# Shruthi-Analog-dev.net
KiCad netlist of a schematic drawn in EAGLE
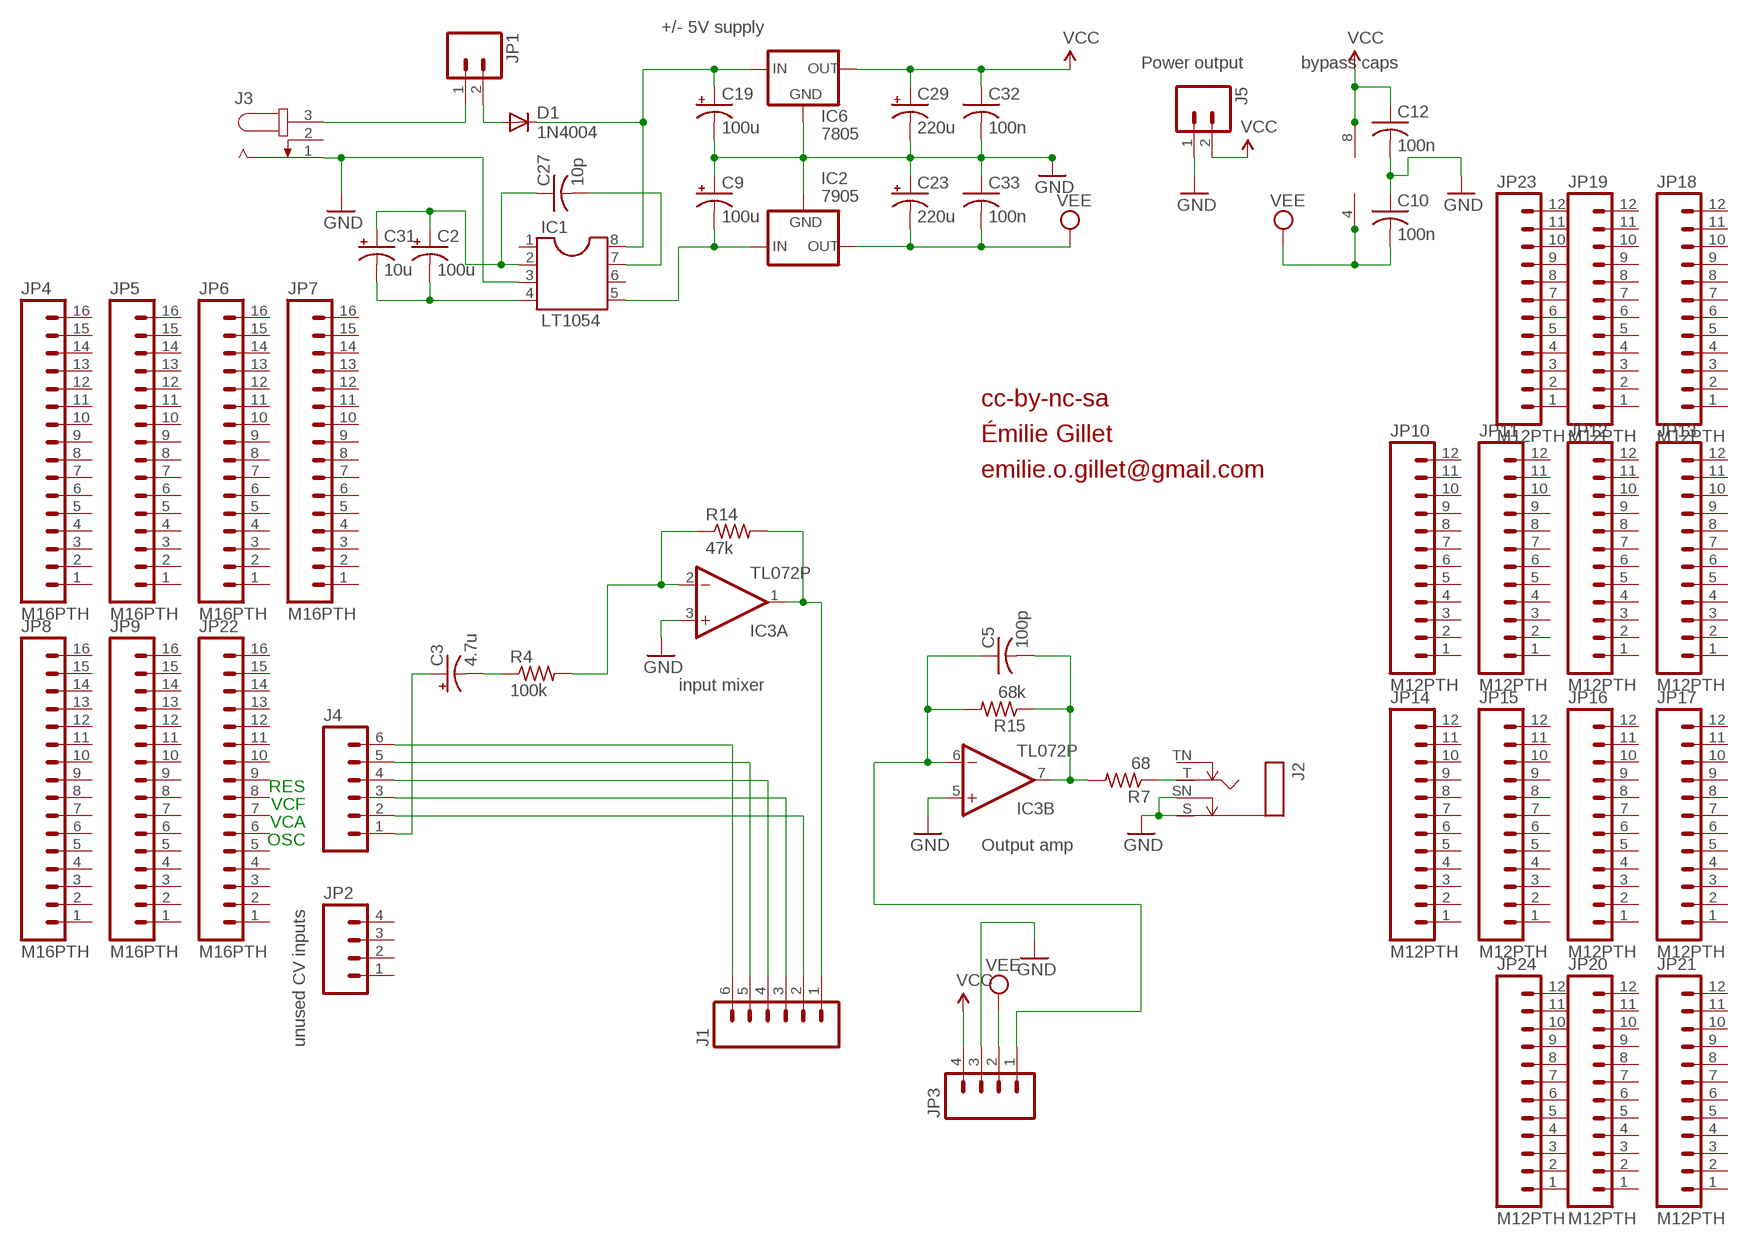
[diagram p0: schematic, sheet 1]

(export (version "E")
  (design (tool "Eeschema 10.0.6"))
  (components
    (comp (ref "C2")
      (value "100u")
      (footprint "eagle-import:E2,5-6")
      (libsource (lib "eagle-import") (part "CPOL-USE2.5-6"))
    )
    (comp (ref "C3")
      (value "4.7u")
      (footprint "eagle-import:E2,5-6")
      (libsource (lib "eagle-import") (part "CPOL-USE2.5-6"))
    )
    (comp (ref "C5")
      (value "100p")
      (footprint "eagle-import:C025-025X050")
      (libsource (lib "eagle-import") (part "C-US025-025X050"))
    )
    (comp (ref "C9")
      (value "100u")
      (footprint "eagle-import:E2,5-7")
      (libsource (lib "eagle-import") (part "CPOL-USE2.5-7"))
    )
    (comp (ref "C10")
      (value "100n")
      (footprint "eagle-import:C025-025X050")
      (libsource (lib "eagle-import") (part "C-US025-025X050"))
    )
    (comp (ref "C12")
      (value "100n")
      (footprint "eagle-import:C025-025X050")
      (libsource (lib "eagle-import") (part "C-US025-025X050"))
    )
    (comp (ref "C19")
      (value "100u")
      (footprint "eagle-import:E2,5-7")
      (libsource (lib "eagle-import") (part "CPOL-USE2.5-7"))
    )
    (comp (ref "C23")
      (value "220u")
      (footprint "eagle-import:E5-10,5")
      (libsource (lib "eagle-import") (part "CPOL-USE5-10.5"))
    )
    (comp (ref "C27")
      (value "10p")
      (footprint "eagle-import:C025-025X050")
      (libsource (lib "eagle-import") (part "C-US025-025X050"))
    )
    (comp (ref "C29")
      (value "220u")
      (footprint "eagle-import:E5-10,5")
      (libsource (lib "eagle-import") (part "CPOL-USE5-10.5"))
    )
    (comp (ref "C31")
      (value "10u")
      (footprint "eagle-import:E2,5-5")
      (libsource (lib "eagle-import") (part "CPOL-USE2.5-5"))
    )
    (comp (ref "C32")
      (value "100n")
      (footprint "eagle-import:C025-025X050")
      (libsource (lib "eagle-import") (part "C-US025-025X050"))
    )
    (comp (ref "C33")
      (value "100n")
      (footprint "eagle-import:C025-025X050")
      (libsource (lib "eagle-import") (part "C-US025-025X050"))
    )
    (comp (ref "D1")
      (value "1N4004")
      (footprint "eagle-import:DO41-10")
      (libsource (lib "eagle-import") (part "1N4004"))
    )
    (comp (ref "IC1")
      (value "LT1054")
      (footprint "eagle-import:DIL08")
      (libsource (lib "eagle-import") (part "DIL8"))
    )
    (comp (ref "IC2")
      (value "7905")
      (footprint "eagle-import:79XXS")
      (libsource (lib "eagle-import") (part "79XXS"))
    )
    (comp (ref "IC3")
      (value "TL072P")
      (footprint "eagle-import:DIL08")
      (libsource (lib "eagle-import") (part "TL072P"))
    )
    (comp (ref "IC6")
      (value "7805")
      (footprint "eagle-import:78XXS")
      (libsource (lib "eagle-import") (part "78XXS"))
    )
    (comp (ref "J1")
      (value "M06SIP")
      (footprint "eagle-import:1X06")
      (libsource (lib "eagle-import") (part "M06SIP"))
    )
    (comp (ref "J2")
      (value "MONOSWS")
      (footprint "eagle-import:NMJ4HC-S")
      (libsource (lib "eagle-import") (part "MONOSWS"))
    )
    (comp (ref "J3")
      (value "JACK-PLUG")
      (footprint "eagle-import:SPC4078_LARGER_HOLES")
      (libsource (lib "eagle-import") (part "JACK-PLUG"))
    )
    (comp (ref "J4")
      (value "M06SIP")
      (footprint "eagle-import:1X06")
      (libsource (lib "eagle-import") (part "M06SIP"))
    )
    (comp (ref "J5")
      (value "M02PTH")
      (footprint "eagle-import:1X02")
      (libsource (lib "eagle-import") (part "M02PTH"))
    )
    (comp (ref "JP1")
      (value "M02")
      (footprint "eagle-import:1X02_LONGPADS")
      (libsource (lib "eagle-import") (part "M02"))
    )
    (comp (ref "JP2")
      (value "M04PTH")
      (footprint "eagle-import:1X04")
      (libsource (lib "eagle-import") (part "M04PTH"))
    )
    (comp (ref "JP3")
      (value "M04PTH")
      (footprint "eagle-import:1X04")
      (libsource (lib "eagle-import") (part "M04PTH"))
    )
    (comp (ref "JP4")
      (value "M16PTH")
      (footprint "eagle-import:1X16")
      (libsource (lib "eagle-import") (part "M16PTH"))
    )
    (comp (ref "JP5")
      (value "M16PTH")
      (footprint "eagle-import:1X16")
      (libsource (lib "eagle-import") (part "M16PTH"))
    )
    (comp (ref "JP6")
      (value "M16PTH")
      (footprint "eagle-import:1X16")
      (libsource (lib "eagle-import") (part "M16PTH"))
    )
    (comp (ref "JP7")
      (value "M16PTH")
      (footprint "eagle-import:1X16")
      (libsource (lib "eagle-import") (part "M16PTH"))
    )
    (comp (ref "JP8")
      (value "M16PTH")
      (footprint "eagle-import:1X16")
      (libsource (lib "eagle-import") (part "M16PTH"))
    )
    (comp (ref "JP9")
      (value "M16PTH")
      (footprint "eagle-import:1X16")
      (libsource (lib "eagle-import") (part "M16PTH"))
    )
    (comp (ref "JP10")
      (value "M12PTH")
      (footprint "eagle-import:1X12")
      (libsource (lib "eagle-import") (part "M12PTH"))
    )
    (comp (ref "JP11")
      (value "M12PTH")
      (footprint "eagle-import:1X12")
      (libsource (lib "eagle-import") (part "M12PTH"))
    )
    (comp (ref "JP12")
      (value "M12PTH")
      (footprint "eagle-import:1X12")
      (libsource (lib "eagle-import") (part "M12PTH"))
    )
    (comp (ref "JP13")
      (value "M12PTH")
      (footprint "eagle-import:1X12")
      (libsource (lib "eagle-import") (part "M12PTH"))
    )
    (comp (ref "JP14")
      (value "M12PTH")
      (footprint "eagle-import:1X12")
      (libsource (lib "eagle-import") (part "M12PTH"))
    )
    (comp (ref "JP15")
      (value "M12PTH")
      (footprint "eagle-import:1X12")
      (libsource (lib "eagle-import") (part "M12PTH"))
    )
    (comp (ref "JP16")
      (value "M12PTH")
      (footprint "eagle-import:1X12")
      (libsource (lib "eagle-import") (part "M12PTH"))
    )
    (comp (ref "JP17")
      (value "M12PTH")
      (footprint "eagle-import:1X12")
      (libsource (lib "eagle-import") (part "M12PTH"))
    )
    (comp (ref "JP18")
      (value "M12PTH")
      (footprint "eagle-import:1X12")
      (libsource (lib "eagle-import") (part "M12PTH"))
    )
    (comp (ref "JP19")
      (value "M12PTH")
      (footprint "eagle-import:1X12")
      (libsource (lib "eagle-import") (part "M12PTH"))
    )
    (comp (ref "JP20")
      (value "M12PTH")
      (footprint "eagle-import:1X12")
      (libsource (lib "eagle-import") (part "M12PTH"))
    )
    (comp (ref "JP21")
      (value "M12PTH")
      (footprint "eagle-import:1X12")
      (libsource (lib "eagle-import") (part "M12PTH"))
    )
    (comp (ref "JP22")
      (value "M16PTH")
      (footprint "eagle-import:1X16")
      (libsource (lib "eagle-import") (part "M16PTH"))
    )
    (comp (ref "JP23")
      (value "M12PTH")
      (footprint "eagle-import:1X12")
      (libsource (lib "eagle-import") (part "M12PTH"))
    )
    (comp (ref "JP24")
      (value "M12PTH")
      (footprint "eagle-import:1X12")
      (libsource (lib "eagle-import") (part "M12PTH"))
    )
    (comp (ref "R4")
      (value "100k")
      (footprint "eagle-import:0204_7")
      (libsource (lib "eagle-import") (part "R-US_0204/7"))
    )
    (comp (ref "R7")
      (value "68")
      (footprint "eagle-import:0204_7")
      (libsource (lib "eagle-import") (part "R-US_0204/7"))
    )
    (comp (ref "R14")
      (value "47k")
      (footprint "eagle-import:0204_7")
      (libsource (lib "eagle-import") (part "R-US_0204/7"))
    )
    (comp (ref "R15")
      (value "68k")
      (footprint "eagle-import:0204_7")
      (libsource (lib "eagle-import") (part "R-US_0204/7"))
    )
  )
  (nets
    (net (code "1") (name "GND") (class "Default")
      (node (ref "C10") (pin "1") (pinfunction "1_1") (pintype "passive"))
      (node (ref "C12") (pin "2") (pinfunction "2_2") (pintype "passive"))
      (node (ref "C19") (pin "-") (pinfunction "-_-") (pintype "passive"))
      (node (ref "C23") (pin "+") (pinfunction "+_+") (pintype "passive"))
      (node (ref "C29") (pin "-") (pinfunction "-_-") (pintype "passive"))
      (node (ref "C32") (pin "2") (pinfunction "2_2") (pintype "passive"))
      (node (ref "C33") (pin "1") (pinfunction "1_1") (pintype "passive"))
      (node (ref "C9") (pin "+") (pinfunction "+_+") (pintype "passive"))
      (node (ref "IC1") (pin "3") (pinfunction "3_3") (pintype "passive"))
      (node (ref "IC2") (pin "GND") (pinfunction "GND_GND") (pintype "input"))
      (node (ref "IC3") (pin "3") (pinfunction "+IN_3") (pintype "input"))
      (node (ref "IC3") (pin "5") (pinfunction "+IN_5") (pintype "input"))
      (node (ref "IC6") (pin "GND") (pinfunction "GND_GND") (pintype "input"))
      (node (ref "J2") (pin "S") (pinfunction "S_S") (pintype "passive"))
      (node (ref "J2") (pin "SN") (pinfunction "SN_SN") (pintype "passive"))
      (node (ref "J3") (pin "1") (pinfunction "1_1") (pintype "passive"))
      (node (ref "J5") (pin "1") (pinfunction "1_1") (pintype "passive"))
      (node (ref "JP3") (pin "3") (pinfunction "3_3") (pintype "passive"))
    )
    (net (code "2") (name "Net-(C2-Pad+)") (class "Default")
      (node (ref "C2") (pin "+") (pinfunction "+_+") (pintype "passive"))
      (node (ref "C27") (pin "1") (pinfunction "1_1") (pintype "passive"))
      (node (ref "C31") (pin "+") (pinfunction "+_+") (pintype "passive"))
      (node (ref "IC1") (pin "2") (pinfunction "2_2") (pintype "passive"))
    )
    (net (code "3") (name "Net-(C2-Pad-)") (class "Default")
      (node (ref "C2") (pin "-") (pinfunction "-_-") (pintype "passive"))
      (node (ref "C31") (pin "-") (pinfunction "-_-") (pintype "passive"))
      (node (ref "IC1") (pin "4") (pinfunction "4_4") (pintype "passive"))
    )
    (net (code "4") (name "Net-(C3-Pad+)") (class "Default")
      (node (ref "C3") (pin "+") (pinfunction "+_+") (pintype "passive"))
      (node (ref "J4") (pin "1") (pinfunction "1_1") (pintype "passive"))
    )
    (net (code "5") (name "Net-(C3-Pad-)") (class "Default")
      (node (ref "C3") (pin "-") (pinfunction "-_-") (pintype "passive"))
      (node (ref "R4") (pin "1") (pinfunction "1_1") (pintype "passive"))
    )
    (net (code "6") (name "Net-(C9-Pad-)") (class "Default")
      (node (ref "C9") (pin "-") (pinfunction "-_-") (pintype "passive"))
      (node (ref "IC1") (pin "5") (pinfunction "5_5") (pintype "passive"))
      (node (ref "IC2") (pin "IN") (pinfunction "IN_IN") (pintype "input"))
    )
    (net (code "7") (name "Net-(C19-Pad+)") (class "Default")
      (node (ref "C19") (pin "+") (pinfunction "+_+") (pintype "passive"))
      (node (ref "D1") (pin "C") (pinfunction "C_C") (pintype "passive"))
      (node (ref "IC1") (pin "8") (pinfunction "8_8") (pintype "passive"))
      (node (ref "IC6") (pin "IN") (pinfunction "IN_IN") (pintype "input"))
    )
    (net (code "8") (name "Net-(C27-Pad2)") (class "Default")
      (node (ref "C27") (pin "2") (pinfunction "2_2") (pintype "passive"))
      (node (ref "IC1") (pin "7") (pinfunction "7_7") (pintype "passive"))
    )
    (net (code "9") (name "Net-(D1-PadA)") (class "Default")
      (node (ref "D1") (pin "A") (pinfunction "A_A") (pintype "passive"))
      (node (ref "JP1") (pin "2") (pinfunction "2_2") (pintype "passive"))
    )
    (net (code "10") (name "Net-(IC3A--IN)") (class "Default")
      (node (ref "IC3") (pin "2") (pinfunction "-IN_2") (pintype "input"))
      (node (ref "R14") (pin "1") (pinfunction "1_1") (pintype "passive"))
      (node (ref "R4") (pin "2") (pinfunction "2_2") (pintype "passive"))
    )
    (net (code "11") (name "Net-(IC3A-OUT)") (class "Default")
      (node (ref "IC3") (pin "1") (pinfunction "OUT_1") (pintype "output"))
      (node (ref "J1") (pin "1") (pinfunction "1_1") (pintype "passive"))
      (node (ref "R14") (pin "2") (pinfunction "2_2") (pintype "passive"))
    )
    (net (code "12") (name "Net-(IC3B--IN)") (class "Default")
      (node (ref "C5") (pin "1") (pinfunction "1_1") (pintype "passive"))
      (node (ref "IC3") (pin "6") (pinfunction "-IN_6") (pintype "input"))
      (node (ref "JP3") (pin "1") (pinfunction "1_1") (pintype "passive"))
      (node (ref "R15") (pin "2") (pinfunction "2_2") (pintype "passive"))
    )
    (net (code "13") (name "Net-(IC3B-OUT)") (class "Default")
      (node (ref "C5") (pin "2") (pinfunction "2_2") (pintype "passive"))
      (node (ref "IC3") (pin "7") (pinfunction "OUT_7") (pintype "output"))
      (node (ref "R15") (pin "1") (pinfunction "1_1") (pintype "passive"))
      (node (ref "R7") (pin "2") (pinfunction "2_2") (pintype "passive"))
    )
    (net (code "14") (name "Net-(J1-Pad2)") (class "Default")
      (node (ref "J1") (pin "2") (pinfunction "2_2") (pintype "passive"))
      (node (ref "J4") (pin "2") (pinfunction "2_2") (pintype "passive"))
    )
    (net (code "15") (name "Net-(J1-Pad3)") (class "Default")
      (node (ref "J1") (pin "3") (pinfunction "3_3") (pintype "passive"))
      (node (ref "J4") (pin "3") (pinfunction "3_3") (pintype "passive"))
    )
    (net (code "16") (name "Net-(J1-Pad4)") (class "Default")
      (node (ref "J1") (pin "4") (pinfunction "4_4") (pintype "passive"))
      (node (ref "J4") (pin "4") (pinfunction "4_4") (pintype "passive"))
    )
    (net (code "17") (name "Net-(J1-Pad5)") (class "Default")
      (node (ref "J1") (pin "5") (pinfunction "5_5") (pintype "passive"))
      (node (ref "J4") (pin "5") (pinfunction "5_5") (pintype "passive"))
    )
    (net (code "18") (name "Net-(J1-Pad6)") (class "Default")
      (node (ref "J1") (pin "6") (pinfunction "6_6") (pintype "passive"))
      (node (ref "J4") (pin "6") (pinfunction "6_6") (pintype "passive"))
    )
    (net (code "19") (name "Net-(J2-PadT)") (class "Default")
      (node (ref "J2") (pin "T") (pinfunction "T_T") (pintype "passive"))
      (node (ref "R7") (pin "1") (pinfunction "1_1") (pintype "passive"))
    )
    (net (code "20") (name "Net-(J3-Pad3)") (class "Default")
      (node (ref "J3") (pin "3") (pinfunction "3_3") (pintype "passive"))
      (node (ref "JP1") (pin "1") (pinfunction "1_1") (pintype "passive"))
    )
    (net (code "21") (name "VCC") (class "Default")
      (node (ref "C12") (pin "1") (pinfunction "1_1") (pintype "passive"))
      (node (ref "C29") (pin "+") (pinfunction "+_+") (pintype "passive"))
      (node (ref "C32") (pin "1") (pinfunction "1_1") (pintype "passive"))
      (node (ref "IC3") (pin "8") (pinfunction "V+_8") (pintype "power_in"))
      (node (ref "IC6") (pin "OUT") (pinfunction "OUT_OUT") (pintype "passive"))
      (node (ref "J5") (pin "2") (pinfunction "2_2") (pintype "passive"))
      (node (ref "JP3") (pin "4") (pinfunction "4_4") (pintype "passive"))
    )
    (net (code "22") (name "VEE") (class "Default")
      (node (ref "C10") (pin "2") (pinfunction "2_2") (pintype "passive"))
      (node (ref "C23") (pin "-") (pinfunction "-_-") (pintype "passive"))
      (node (ref "C33") (pin "2") (pinfunction "2_2") (pintype "passive"))
      (node (ref "IC2") (pin "OUT") (pinfunction "OUT_OUT") (pintype "passive"))
      (node (ref "IC3") (pin "4") (pinfunction "V-_4") (pintype "power_in"))
      (node (ref "JP3") (pin "2") (pinfunction "2_2") (pintype "passive"))
    )
    (net (code "23") (name "unconnected-(IC1-Pad1)") (class "Default")
      (node (ref "IC1") (pin "1") (pinfunction "1_1") (pintype "passive"))
    )
    (net (code "24") (name "unconnected-(IC1-Pad6)") (class "Default")
      (node (ref "IC1") (pin "6") (pinfunction "6_6") (pintype "passive"))
    )
    (net (code "25") (name "unconnected-(J2-PadTN)") (class "Default")
      (node (ref "J2") (pin "TN") (pinfunction "TN_TN") (pintype "passive"))
    )
    (net (code "26") (name "unconnected-(J3-Pad2)") (class "Default")
      (node (ref "J3") (pin "2") (pinfunction "2_2") (pintype "passive"))
    )
    (net (code "27") (name "unconnected-(JP2-Pad1)") (class "Default")
      (node (ref "JP2") (pin "1") (pinfunction "1_1") (pintype "passive"))
    )
    (net (code "28") (name "unconnected-(JP2-Pad2)") (class "Default")
      (node (ref "JP2") (pin "2") (pinfunction "2_2") (pintype "passive"))
    )
    (net (code "29") (name "unconnected-(JP2-Pad3)") (class "Default")
      (node (ref "JP2") (pin "3") (pinfunction "3_3") (pintype "passive"))
    )
    (net (code "30") (name "unconnected-(JP2-Pad4)") (class "Default")
      (node (ref "JP2") (pin "4") (pinfunction "4_4") (pintype "passive"))
    )
    (net (code "31") (name "unconnected-(JP4-Pad1)") (class "Default")
      (node (ref "JP4") (pin "1") (pinfunction "1_1") (pintype "passive"))
    )
    (net (code "32") (name "unconnected-(JP4-Pad2)") (class "Default")
      (node (ref "JP4") (pin "2") (pinfunction "2_2") (pintype "passive"))
    )
    (net (code "33") (name "unconnected-(JP4-Pad3)") (class "Default")
      (node (ref "JP4") (pin "3") (pinfunction "3_3") (pintype "passive"))
    )
    (net (code "34") (name "unconnected-(JP4-Pad4)") (class "Default")
      (node (ref "JP4") (pin "4") (pinfunction "4_4") (pintype "passive"))
    )
    (net (code "35") (name "unconnected-(JP4-Pad5)") (class "Default")
      (node (ref "JP4") (pin "5") (pinfunction "5_5") (pintype "passive"))
    )
    (net (code "36") (name "unconnected-(JP4-Pad6)") (class "Default")
      (node (ref "JP4") (pin "6") (pinfunction "6_6") (pintype "passive"))
    )
    (net (code "37") (name "unconnected-(JP4-Pad7)") (class "Default")
      (node (ref "JP4") (pin "7") (pinfunction "7_7") (pintype "passive"))
    )
    (net (code "38") (name "unconnected-(JP4-Pad8)") (class "Default")
      (node (ref "JP4") (pin "8") (pinfunction "8_8") (pintype "passive"))
    )
    (net (code "39") (name "unconnected-(JP4-Pad9)") (class "Default")
      (node (ref "JP4") (pin "9") (pinfunction "9_9") (pintype "passive"))
    )
    (net (code "40") (name "unconnected-(JP4-Pad10)") (class "Default")
      (node (ref "JP4") (pin "10") (pinfunction "10_10") (pintype "passive"))
    )
    (net (code "41") (name "unconnected-(JP4-Pad11)") (class "Default")
      (node (ref "JP4") (pin "11") (pinfunction "11_11") (pintype "passive"))
    )
    (net (code "42") (name "unconnected-(JP4-Pad12)") (class "Default")
      (node (ref "JP4") (pin "12") (pinfunction "12_12") (pintype "passive"))
    )
    (net (code "43") (name "unconnected-(JP4-Pad13)") (class "Default")
      (node (ref "JP4") (pin "13") (pinfunction "13_13") (pintype "passive"))
    )
    (net (code "44") (name "unconnected-(JP4-Pad14)") (class "Default")
      (node (ref "JP4") (pin "14") (pinfunction "14_14") (pintype "passive"))
    )
    (net (code "45") (name "unconnected-(JP4-Pad15)") (class "Default")
      (node (ref "JP4") (pin "15") (pinfunction "15_15") (pintype "passive"))
    )
    (net (code "46") (name "unconnected-(JP4-Pad16)") (class "Default")
      (node (ref "JP4") (pin "16") (pinfunction "16_16") (pintype "passive"))
    )
    (net (code "47") (name "unconnected-(JP5-Pad1)") (class "Default")
      (node (ref "JP5") (pin "1") (pinfunction "1_1") (pintype "passive"))
    )
    (net (code "48") (name "unconnected-(JP5-Pad2)") (class "Default")
      (node (ref "JP5") (pin "2") (pinfunction "2_2") (pintype "passive"))
    )
    (net (code "49") (name "unconnected-(JP5-Pad3)") (class "Default")
      (node (ref "JP5") (pin "3") (pinfunction "3_3") (pintype "passive"))
    )
    (net (code "50") (name "unconnected-(JP5-Pad4)") (class "Default")
      (node (ref "JP5") (pin "4") (pinfunction "4_4") (pintype "passive"))
    )
    (net (code "51") (name "unconnected-(JP5-Pad5)") (class "Default")
      (node (ref "JP5") (pin "5") (pinfunction "5_5") (pintype "passive"))
    )
    (net (code "52") (name "unconnected-(JP5-Pad6)") (class "Default")
      (node (ref "JP5") (pin "6") (pinfunction "6_6") (pintype "passive"))
    )
    (net (code "53") (name "unconnected-(JP5-Pad7)") (class "Default")
      (node (ref "JP5") (pin "7") (pinfunction "7_7") (pintype "passive"))
    )
    (net (code "54") (name "unconnected-(JP5-Pad8)") (class "Default")
      (node (ref "JP5") (pin "8") (pinfunction "8_8") (pintype "passive"))
    )
    (net (code "55") (name "unconnected-(JP5-Pad9)") (class "Default")
      (node (ref "JP5") (pin "9") (pinfunction "9_9") (pintype "passive"))
    )
    (net (code "56") (name "unconnected-(JP5-Pad10)") (class "Default")
      (node (ref "JP5") (pin "10") (pinfunction "10_10") (pintype "passive"))
    )
    (net (code "57") (name "unconnected-(JP5-Pad11)") (class "Default")
      (node (ref "JP5") (pin "11") (pinfunction "11_11") (pintype "passive"))
    )
    (net (code "58") (name "unconnected-(JP5-Pad12)") (class "Default")
      (node (ref "JP5") (pin "12") (pinfunction "12_12") (pintype "passive"))
    )
    (net (code "59") (name "unconnected-(JP5-Pad13)") (class "Default")
      (node (ref "JP5") (pin "13") (pinfunction "13_13") (pintype "passive"))
    )
    (net (code "60") (name "unconnected-(JP5-Pad14)") (class "Default")
      (node (ref "JP5") (pin "14") (pinfunction "14_14") (pintype "passive"))
    )
    (net (code "61") (name "unconnected-(JP5-Pad15)") (class "Default")
      (node (ref "JP5") (pin "15") (pinfunction "15_15") (pintype "passive"))
    )
    (net (code "62") (name "unconnected-(JP5-Pad16)") (class "Default")
      (node (ref "JP5") (pin "16") (pinfunction "16_16") (pintype "passive"))
    )
    (net (code "63") (name "unconnected-(JP6-Pad1)") (class "Default")
      (node (ref "JP6") (pin "1") (pinfunction "1_1") (pintype "passive"))
    )
    (net (code "64") (name "unconnected-(JP6-Pad2)") (class "Default")
      (node (ref "JP6") (pin "2") (pinfunction "2_2") (pintype "passive"))
    )
    (net (code "65") (name "unconnected-(JP6-Pad3)") (class "Default")
      (node (ref "JP6") (pin "3") (pinfunction "3_3") (pintype "passive"))
    )
    (net (code "66") (name "unconnected-(JP6-Pad4)") (class "Default")
      (node (ref "JP6") (pin "4") (pinfunction "4_4") (pintype "passive"))
    )
    (net (code "67") (name "unconnected-(JP6-Pad5)") (class "Default")
      (node (ref "JP6") (pin "5") (pinfunction "5_5") (pintype "passive"))
    )
    (net (code "68") (name "unconnected-(JP6-Pad6)") (class "Default")
      (node (ref "JP6") (pin "6") (pinfunction "6_6") (pintype "passive"))
    )
    (net (code "69") (name "unconnected-(JP6-Pad7)") (class "Default")
      (node (ref "JP6") (pin "7") (pinfunction "7_7") (pintype "passive"))
    )
    (net (code "70") (name "unconnected-(JP6-Pad8)") (class "Default")
      (node (ref "JP6") (pin "8") (pinfunction "8_8") (pintype "passive"))
    )
    (net (code "71") (name "unconnected-(JP6-Pad9)") (class "Default")
      (node (ref "JP6") (pin "9") (pinfunction "9_9") (pintype "passive"))
    )
    (net (code "72") (name "unconnected-(JP6-Pad10)") (class "Default")
      (node (ref "JP6") (pin "10") (pinfunction "10_10") (pintype "passive"))
    )
    (net (code "73") (name "unconnected-(JP6-Pad11)") (class "Default")
      (node (ref "JP6") (pin "11") (pinfunction "11_11") (pintype "passive"))
    )
    (net (code "74") (name "unconnected-(JP6-Pad12)") (class "Default")
      (node (ref "JP6") (pin "12") (pinfunction "12_12") (pintype "passive"))
    )
    (net (code "75") (name "unconnected-(JP6-Pad13)") (class "Default")
      (node (ref "JP6") (pin "13") (pinfunction "13_13") (pintype "passive"))
    )
    (net (code "76") (name "unconnected-(JP6-Pad14)") (class "Default")
      (node (ref "JP6") (pin "14") (pinfunction "14_14") (pintype "passive"))
    )
    (net (code "77") (name "unconnected-(JP6-Pad15)") (class "Default")
      (node (ref "JP6") (pin "15") (pinfunction "15_15") (pintype "passive"))
    )
    (net (code "78") (name "unconnected-(JP6-Pad16)") (class "Default")
      (node (ref "JP6") (pin "16") (pinfunction "16_16") (pintype "passive"))
    )
    (net (code "79") (name "unconnected-(JP7-Pad1)") (class "Default")
      (node (ref "JP7") (pin "1") (pinfunction "1_1") (pintype "passive"))
    )
    (net (code "80") (name "unconnected-(JP7-Pad2)") (class "Default")
      (node (ref "JP7") (pin "2") (pinfunction "2_2") (pintype "passive"))
    )
    (net (code "81") (name "unconnected-(JP7-Pad3)") (class "Default")
      (node (ref "JP7") (pin "3") (pinfunction "3_3") (pintype "passive"))
    )
    (net (code "82") (name "unconnected-(JP7-Pad4)") (class "Default")
      (node (ref "JP7") (pin "4") (pinfunction "4_4") (pintype "passive"))
    )
    (net (code "83") (name "unconnected-(JP7-Pad5)") (class "Default")
      (node (ref "JP7") (pin "5") (pinfunction "5_5") (pintype "passive"))
    )
    (net (code "84") (name "unconnected-(JP7-Pad6)") (class "Default")
      (node (ref "JP7") (pin "6") (pinfunction "6_6") (pintype "passive"))
    )
    (net (code "85") (name "unconnected-(JP7-Pad7)") (class "Default")
      (node (ref "JP7") (pin "7") (pinfunction "7_7") (pintype "passive"))
    )
    (net (code "86") (name "unconnected-(JP7-Pad8)") (class "Default")
      (node (ref "JP7") (pin "8") (pinfunction "8_8") (pintype "passive"))
    )
    (net (code "87") (name "unconnected-(JP7-Pad9)") (class "Default")
      (node (ref "JP7") (pin "9") (pinfunction "9_9") (pintype "passive"))
    )
    (net (code "88") (name "unconnected-(JP7-Pad10)") (class "Default")
      (node (ref "JP7") (pin "10") (pinfunction "10_10") (pintype "passive"))
    )
    (net (code "89") (name "unconnected-(JP7-Pad11)") (class "Default")
      (node (ref "JP7") (pin "11") (pinfunction "11_11") (pintype "passive"))
    )
    (net (code "90") (name "unconnected-(JP7-Pad12)") (class "Default")
      (node (ref "JP7") (pin "12") (pinfunction "12_12") (pintype "passive"))
    )
    (net (code "91") (name "unconnected-(JP7-Pad13)") (class "Default")
      (node (ref "JP7") (pin "13") (pinfunction "13_13") (pintype "passive"))
    )
    (net (code "92") (name "unconnected-(JP7-Pad14)") (class "Default")
      (node (ref "JP7") (pin "14") (pinfunction "14_14") (pintype "passive"))
    )
    (net (code "93") (name "unconnected-(JP7-Pad15)") (class "Default")
      (node (ref "JP7") (pin "15") (pinfunction "15_15") (pintype "passive"))
    )
    (net (code "94") (name "unconnected-(JP7-Pad16)") (class "Default")
      (node (ref "JP7") (pin "16") (pinfunction "16_16") (pintype "passive"))
    )
    (net (code "95") (name "unconnected-(JP8-Pad1)") (class "Default")
      (node (ref "JP8") (pin "1") (pinfunction "1_1") (pintype "passive"))
    )
    (net (code "96") (name "unconnected-(JP8-Pad2)") (class "Default")
      (node (ref "JP8") (pin "2") (pinfunction "2_2") (pintype "passive"))
    )
    (net (code "97") (name "unconnected-(JP8-Pad3)") (class "Default")
      (node (ref "JP8") (pin "3") (pinfunction "3_3") (pintype "passive"))
    )
    (net (code "98") (name "unconnected-(JP8-Pad4)") (class "Default")
      (node (ref "JP8") (pin "4") (pinfunction "4_4") (pintype "passive"))
    )
    (net (code "99") (name "unconnected-(JP8-Pad5)") (class "Default")
      (node (ref "JP8") (pin "5") (pinfunction "5_5") (pintype "passive"))
    )
    (net (code "100") (name "unconnected-(JP8-Pad6)") (class "Default")
      (node (ref "JP8") (pin "6") (pinfunction "6_6") (pintype "passive"))
    )
    (net (code "101") (name "unconnected-(JP8-Pad7)") (class "Default")
      (node (ref "JP8") (pin "7") (pinfunction "7_7") (pintype "passive"))
    )
    (net (code "102") (name "unconnected-(JP8-Pad8)") (class "Default")
      (node (ref "JP8") (pin "8") (pinfunction "8_8") (pintype "passive"))
    )
    (net (code "103") (name "unconnected-(JP8-Pad9)") (class "Default")
      (node (ref "JP8") (pin "9") (pinfunction "9_9") (pintype "passive"))
    )
    (net (code "104") (name "unconnected-(JP8-Pad10)") (class "Default")
      (node (ref "JP8") (pin "10") (pinfunction "10_10") (pintype "passive"))
    )
    (net (code "105") (name "unconnected-(JP8-Pad11)") (class "Default")
      (node (ref "JP8") (pin "11") (pinfunction "11_11") (pintype "passive"))
    )
    (net (code "106") (name "unconnected-(JP8-Pad12)") (class "Default")
      (node (ref "JP8") (pin "12") (pinfunction "12_12") (pintype "passive"))
    )
    (net (code "107") (name "unconnected-(JP8-Pad13)") (class "Default")
      (node (ref "JP8") (pin "13") (pinfunction "13_13") (pintype "passive"))
    )
    (net (code "108") (name "unconnected-(JP8-Pad14)") (class "Default")
      (node (ref "JP8") (pin "14") (pinfunction "14_14") (pintype "passive"))
    )
    (net (code "109") (name "unconnected-(JP8-Pad15)") (class "Default")
      (node (ref "JP8") (pin "15") (pinfunction "15_15") (pintype "passive"))
    )
    (net (code "110") (name "unconnected-(JP8-Pad16)") (class "Default")
      (node (ref "JP8") (pin "16") (pinfunction "16_16") (pintype "passive"))
    )
    (net (code "111") (name "unconnected-(JP9-Pad1)") (class "Default")
      (node (ref "JP9") (pin "1") (pinfunction "1_1") (pintype "passive"))
    )
    (net (code "112") (name "unconnected-(JP9-Pad2)") (class "Default")
      (node (ref "JP9") (pin "2") (pinfunction "2_2") (pintype "passive"))
    )
    (net (code "113") (name "unconnected-(JP9-Pad3)") (class "Default")
      (node (ref "JP9") (pin "3") (pinfunction "3_3") (pintype "passive"))
    )
    (net (code "114") (name "unconnected-(JP9-Pad4)") (class "Default")
      (node (ref "JP9") (pin "4") (pinfunction "4_4") (pintype "passive"))
    )
    (net (code "115") (name "unconnected-(JP9-Pad5)") (class "Default")
      (node (ref "JP9") (pin "5") (pinfunction "5_5") (pintype "passive"))
    )
    (net (code "116") (name "unconnected-(JP9-Pad6)") (class "Default")
      (node (ref "JP9") (pin "6") (pinfunction "6_6") (pintype "passive"))
    )
    (net (code "117") (name "unconnected-(JP9-Pad7)") (class "Default")
      (node (ref "JP9") (pin "7") (pinfunction "7_7") (pintype "passive"))
    )
    (net (code "118") (name "unconnected-(JP9-Pad8)") (class "Default")
      (node (ref "JP9") (pin "8") (pinfunction "8_8") (pintype "passive"))
    )
    (net (code "119") (name "unconnected-(JP9-Pad9)") (class "Default")
      (node (ref "JP9") (pin "9") (pinfunction "9_9") (pintype "passive"))
    )
    (net (code "120") (name "unconnected-(JP9-Pad10)") (class "Default")
      (node (ref "JP9") (pin "10") (pinfunction "10_10") (pintype "passive"))
    )
    (net (code "121") (name "unconnected-(JP9-Pad11)") (class "Default")
      (node (ref "JP9") (pin "11") (pinfunction "11_11") (pintype "passive"))
    )
    (net (code "122") (name "unconnected-(JP9-Pad12)") (class "Default")
      (node (ref "JP9") (pin "12") (pinfunction "12_12") (pintype "passive"))
    )
    (net (code "123") (name "unconnected-(JP9-Pad13)") (class "Default")
      (node (ref "JP9") (pin "13") (pinfunction "13_13") (pintype "passive"))
    )
    (net (code "124") (name "unconnected-(JP9-Pad14)") (class "Default")
      (node (ref "JP9") (pin "14") (pinfunction "14_14") (pintype "passive"))
    )
    (net (code "125") (name "unconnected-(JP9-Pad15)") (class "Default")
      (node (ref "JP9") (pin "15") (pinfunction "15_15") (pintype "passive"))
    )
    (net (code "126") (name "unconnected-(JP9-Pad16)") (class "Default")
      (node (ref "JP9") (pin "16") (pinfunction "16_16") (pintype "passive"))
    )
    (net (code "127") (name "unconnected-(JP10-Pad1)") (class "Default")
      (node (ref "JP10") (pin "1") (pinfunction "1_1") (pintype "passive"))
    )
    (net (code "128") (name "unconnected-(JP10-Pad2)") (class "Default")
      (node (ref "JP10") (pin "2") (pinfunction "2_2") (pintype "passive"))
    )
    (net (code "129") (name "unconnected-(JP10-Pad3)") (class "Default")
      (node (ref "JP10") (pin "3") (pinfunction "3_3") (pintype "passive"))
    )
    (net (code "130") (name "unconnected-(JP10-Pad4)") (class "Default")
      (node (ref "JP10") (pin "4") (pinfunction "4_4") (pintype "passive"))
    )
    (net (code "131") (name "unconnected-(JP10-Pad5)") (class "Default")
      (node (ref "JP10") (pin "5") (pinfunction "5_5") (pintype "passive"))
    )
    (net (code "132") (name "unconnected-(JP10-Pad6)") (class "Default")
      (node (ref "JP10") (pin "6") (pinfunction "6_6") (pintype "passive"))
    )
    (net (code "133") (name "unconnected-(JP10-Pad7)") (class "Default")
      (node (ref "JP10") (pin "7") (pinfunction "7_7") (pintype "passive"))
    )
    (net (code "134") (name "unconnected-(JP10-Pad8)") (class "Default")
      (node (ref "JP10") (pin "8") (pinfunction "8_8") (pintype "passive"))
    )
    (net (code "135") (name "unconnected-(JP10-Pad9)") (class "Default")
      (node (ref "JP10") (pin "9") (pinfunction "9_9") (pintype "passive"))
    )
    (net (code "136") (name "unconnected-(JP10-Pad10)") (class "Default")
      (node (ref "JP10") (pin "10") (pinfunction "10_10") (pintype "passive"))
    )
    (net (code "137") (name "unconnected-(JP10-Pad11)") (class "Default")
      (node (ref "JP10") (pin "11") (pinfunction "11_11") (pintype "passive"))
    )
    (net (code "138") (name "unconnected-(JP10-Pad12)") (class "Default")
      (node (ref "JP10") (pin "12") (pinfunction "12_12") (pintype "passive"))
    )
    (net (code "139") (name "unconnected-(JP11-Pad1)") (class "Default")
      (node (ref "JP11") (pin "1") (pinfunction "1_1") (pintype "passive"))
    )
    (net (code "140") (name "unconnected-(JP11-Pad2)") (class "Default")
      (node (ref "JP11") (pin "2") (pinfunction "2_2") (pintype "passive"))
    )
    (net (code "141") (name "unconnected-(JP11-Pad3)") (class "Default")
      (node (ref "JP11") (pin "3") (pinfunction "3_3") (pintype "passive"))
    )
    (net (code "142") (name "unconnected-(JP11-Pad4)") (class "Default")
      (node (ref "JP11") (pin "4") (pinfunction "4_4") (pintype "passive"))
    )
    (net (code "143") (name "unconnected-(JP11-Pad5)") (class "Default")
      (node (ref "JP11") (pin "5") (pinfunction "5_5") (pintype "passive"))
    )
    (net (code "144") (name "unconnected-(JP11-Pad6)") (class "Default")
      (node (ref "JP11") (pin "6") (pinfunction "6_6") (pintype "passive"))
    )
    (net (code "145") (name "unconnected-(JP11-Pad7)") (class "Default")
      (node (ref "JP11") (pin "7") (pinfunction "7_7") (pintype "passive"))
    )
    (net (code "146") (name "unconnected-(JP11-Pad8)") (class "Default")
      (node (ref "JP11") (pin "8") (pinfunction "8_8") (pintype "passive"))
    )
    (net (code "147") (name "unconnected-(JP11-Pad9)") (class "Default")
      (node (ref "JP11") (pin "9") (pinfunction "9_9") (pintype "passive"))
    )
    (net (code "148") (name "unconnected-(JP11-Pad10)") (class "Default")
      (node (ref "JP11") (pin "10") (pinfunction "10_10") (pintype "passive"))
    )
    (net (code "149") (name "unconnected-(JP11-Pad11)") (class "Default")
      (node (ref "JP11") (pin "11") (pinfunction "11_11") (pintype "passive"))
    )
    (net (code "150") (name "unconnected-(JP11-Pad12)") (class "Default")
      (node (ref "JP11") (pin "12") (pinfunction "12_12") (pintype "passive"))
    )
    (net (code "151") (name "unconnected-(JP12-Pad1)") (class "Default")
      (node (ref "JP12") (pin "1") (pinfunction "1_1") (pintype "passive"))
    )
    (net (code "152") (name "unconnected-(JP12-Pad2)") (class "Default")
      (node (ref "JP12") (pin "2") (pinfunction "2_2") (pintype "passive"))
    )
    (net (code "153") (name "unconnected-(JP12-Pad3)") (class "Default")
      (node (ref "JP12") (pin "3") (pinfunction "3_3") (pintype "passive"))
    )
    (net (code "154") (name "unconnected-(JP12-Pad4)") (class "Default")
      (node (ref "JP12") (pin "4") (pinfunction "4_4") (pintype "passive"))
    )
    (net (code "155") (name "unconnected-(JP12-Pad5)") (class "Default")
      (node (ref "JP12") (pin "5") (pinfunction "5_5") (pintype "passive"))
    )
    (net (code "156") (name "unconnected-(JP12-Pad6)") (class "Default")
      (node (ref "JP12") (pin "6") (pinfunction "6_6") (pintype "passive"))
    )
    (net (code "157") (name "unconnected-(JP12-Pad7)") (class "Default")
      (node (ref "JP12") (pin "7") (pinfunction "7_7") (pintype "passive"))
    )
    (net (code "158") (name "unconnected-(JP12-Pad8)") (class "Default")
      (node (ref "JP12") (pin "8") (pinfunction "8_8") (pintype "passive"))
    )
    (net (code "159") (name "unconnected-(JP12-Pad9)") (class "Default")
      (node (ref "JP12") (pin "9") (pinfunction "9_9") (pintype "passive"))
    )
    (net (code "160") (name "unconnected-(JP12-Pad10)") (class "Default")
      (node (ref "JP12") (pin "10") (pinfunction "10_10") (pintype "passive"))
    )
    (net (code "161") (name "unconnected-(JP12-Pad11)") (class "Default")
      (node (ref "JP12") (pin "11") (pinfunction "11_11") (pintype "passive"))
    )
    (net (code "162") (name "unconnected-(JP12-Pad12)") (class "Default")
      (node (ref "JP12") (pin "12") (pinfunction "12_12") (pintype "passive"))
    )
    (net (code "163") (name "unconnected-(JP13-Pad1)") (class "Default")
      (node (ref "JP13") (pin "1") (pinfunction "1_1") (pintype "passive"))
    )
    (net (code "164") (name "unconnected-(JP13-Pad2)") (class "Default")
      (node (ref "JP13") (pin "2") (pinfunction "2_2") (pintype "passive"))
    )
    (net (code "165") (name "unconnected-(JP13-Pad3)") (class "Default")
      (node (ref "JP13") (pin "3") (pinfunction "3_3") (pintype "passive"))
    )
    (net (code "166") (name "unconnected-(JP13-Pad4)") (class "Default")
      (node (ref "JP13") (pin "4") (pinfunction "4_4") (pintype "passive"))
    )
    (net (code "167") (name "unconnected-(JP13-Pad5)") (class "Default")
      (node (ref "JP13") (pin "5") (pinfunction "5_5") (pintype "passive"))
    )
    (net (code "168") (name "unconnected-(JP13-Pad6)") (class "Default")
      (node (ref "JP13") (pin "6") (pinfunction "6_6") (pintype "passive"))
    )
    (net (code "169") (name "unconnected-(JP13-Pad7)") (class "Default")
      (node (ref "JP13") (pin "7") (pinfunction "7_7") (pintype "passive"))
    )
    (net (code "170") (name "unconnected-(JP13-Pad8)") (class "Default")
      (node (ref "JP13") (pin "8") (pinfunction "8_8") (pintype "passive"))
    )
    (net (code "171") (name "unconnected-(JP13-Pad9)") (class "Default")
      (node (ref "JP13") (pin "9") (pinfunction "9_9") (pintype "passive"))
    )
    (net (code "172") (name "unconnected-(JP13-Pad10)") (class "Default")
      (node (ref "JP13") (pin "10") (pinfunction "10_10") (pintype "passive"))
    )
    (net (code "173") (name "unconnected-(JP13-Pad11)") (class "Default")
      (node (ref "JP13") (pin "11") (pinfunction "11_11") (pintype "passive"))
    )
    (net (code "174") (name "unconnected-(JP13-Pad12)") (class "Default")
      (node (ref "JP13") (pin "12") (pinfunction "12_12") (pintype "passive"))
    )
    (net (code "175") (name "unconnected-(JP14-Pad1)") (class "Default")
      (node (ref "JP14") (pin "1") (pinfunction "1_1") (pintype "passive"))
    )
    (net (code "176") (name "unconnected-(JP14-Pad2)") (class "Default")
      (node (ref "JP14") (pin "2") (pinfunction "2_2") (pintype "passive"))
    )
    (net (code "177") (name "unconnected-(JP14-Pad3)") (class "Default")
      (node (ref "JP14") (pin "3") (pinfunction "3_3") (pintype "passive"))
    )
    (net (code "178") (name "unconnected-(JP14-Pad4)") (class "Default")
      (node (ref "JP14") (pin "4") (pinfunction "4_4") (pintype "passive"))
    )
    (net (code "179") (name "unconnected-(JP14-Pad5)") (class "Default")
      (node (ref "JP14") (pin "5") (pinfunction "5_5") (pintype "passive"))
    )
    (net (code "180") (name "unconnected-(JP14-Pad6)") (class "Default")
      (node (ref "JP14") (pin "6") (pinfunction "6_6") (pintype "passive"))
    )
    (net (code "181") (name "unconnected-(JP14-Pad7)") (class "Default")
      (node (ref "JP14") (pin "7") (pinfunction "7_7") (pintype "passive"))
    )
    (net (code "182") (name "unconnected-(JP14-Pad8)") (class "Default")
      (node (ref "JP14") (pin "8") (pinfunction "8_8") (pintype "passive"))
    )
    (net (code "183") (name "unconnected-(JP14-Pad9)") (class "Default")
      (node (ref "JP14") (pin "9") (pinfunction "9_9") (pintype "passive"))
    )
    (net (code "184") (name "unconnected-(JP14-Pad10)") (class "Default")
      (node (ref "JP14") (pin "10") (pinfunction "10_10") (pintype "passive"))
    )
    (net (code "185") (name "unconnected-(JP14-Pad11)") (class "Default")
      (node (ref "JP14") (pin "11") (pinfunction "11_11") (pintype "passive"))
    )
    (net (code "186") (name "unconnected-(JP14-Pad12)") (class "Default")
      (node (ref "JP14") (pin "12") (pinfunction "12_12") (pintype "passive"))
    )
    (net (code "187") (name "unconnected-(JP15-Pad1)") (class "Default")
      (node (ref "JP15") (pin "1") (pinfunction "1_1") (pintype "passive"))
    )
    (net (code "188") (name "unconnected-(JP15-Pad2)") (class "Default")
      (node (ref "JP15") (pin "2") (pinfunction "2_2") (pintype "passive"))
    )
    (net (code "189") (name "unconnected-(JP15-Pad3)") (class "Default")
      (node (ref "JP15") (pin "3") (pinfunction "3_3") (pintype "passive"))
    )
    (net (code "190") (name "unconnected-(JP15-Pad4)") (class "Default")
      (node (ref "JP15") (pin "4") (pinfunction "4_4") (pintype "passive"))
    )
    (net (code "191") (name "unconnected-(JP15-Pad5)") (class "Default")
      (node (ref "JP15") (pin "5") (pinfunction "5_5") (pintype "passive"))
    )
    (net (code "192") (name "unconnected-(JP15-Pad6)") (class "Default")
      (node (ref "JP15") (pin "6") (pinfunction "6_6") (pintype "passive"))
    )
    (net (code "193") (name "unconnected-(JP15-Pad7)") (class "Default")
      (node (ref "JP15") (pin "7") (pinfunction "7_7") (pintype "passive"))
    )
    (net (code "194") (name "unconnected-(JP15-Pad8)") (class "Default")
      (node (ref "JP15") (pin "8") (pinfunction "8_8") (pintype "passive"))
    )
    (net (code "195") (name "unconnected-(JP15-Pad9)") (class "Default")
      (node (ref "JP15") (pin "9") (pinfunction "9_9") (pintype "passive"))
    )
    (net (code "196") (name "unconnected-(JP15-Pad10)") (class "Default")
      (node (ref "JP15") (pin "10") (pinfunction "10_10") (pintype "passive"))
    )
    (net (code "197") (name "unconnected-(JP15-Pad11)") (class "Default")
      (node (ref "JP15") (pin "11") (pinfunction "11_11") (pintype "passive"))
    )
    (net (code "198") (name "unconnected-(JP15-Pad12)") (class "Default")
      (node (ref "JP15") (pin "12") (pinfunction "12_12") (pintype "passive"))
    )
    (net (code "199") (name "unconnected-(JP16-Pad1)") (class "Default")
      (node (ref "JP16") (pin "1") (pinfunction "1_1") (pintype "passive"))
    )
    (net (code "200") (name "unconnected-(JP16-Pad2)") (class "Default")
      (node (ref "JP16") (pin "2") (pinfunction "2_2") (pintype "passive"))
    )
    (net (code "201") (name "unconnected-(JP16-Pad3)") (class "Default")
      (node (ref "JP16") (pin "3") (pinfunction "3_3") (pintype "passive"))
    )
    (net (code "202") (name "unconnected-(JP16-Pad4)") (class "Default")
      (node (ref "JP16") (pin "4") (pinfunction "4_4") (pintype "passive"))
    )
    (net (code "203") (name "unconnected-(JP16-Pad5)") (class "Default")
      (node (ref "JP16") (pin "5") (pinfunction "5_5") (pintype "passive"))
    )
    (net (code "204") (name "unconnected-(JP16-Pad6)") (class "Default")
      (node (ref "JP16") (pin "6") (pinfunction "6_6") (pintype "passive"))
    )
    (net (code "205") (name "unconnected-(JP16-Pad7)") (class "Default")
      (node (ref "JP16") (pin "7") (pinfunction "7_7") (pintype "passive"))
    )
    (net (code "206") (name "unconnected-(JP16-Pad8)") (class "Default")
      (node (ref "JP16") (pin "8") (pinfunction "8_8") (pintype "passive"))
    )
    (net (code "207") (name "unconnected-(JP16-Pad9)") (class "Default")
      (node (ref "JP16") (pin "9") (pinfunction "9_9") (pintype "passive"))
    )
    (net (code "208") (name "unconnected-(JP16-Pad10)") (class "Default")
      (node (ref "JP16") (pin "10") (pinfunction "10_10") (pintype "passive"))
    )
    (net (code "209") (name "unconnected-(JP16-Pad11)") (class "Default")
      (node (ref "JP16") (pin "11") (pinfunction "11_11") (pintype "passive"))
    )
    (net (code "210") (name "unconnected-(JP16-Pad12)") (class "Default")
      (node (ref "JP16") (pin "12") (pinfunction "12_12") (pintype "passive"))
    )
    (net (code "211") (name "unconnected-(JP17-Pad1)") (class "Default")
      (node (ref "JP17") (pin "1") (pinfunction "1_1") (pintype "passive"))
    )
    (net (code "212") (name "unconnected-(JP17-Pad2)") (class "Default")
      (node (ref "JP17") (pin "2") (pinfunction "2_2") (pintype "passive"))
    )
    (net (code "213") (name "unconnected-(JP17-Pad3)") (class "Default")
      (node (ref "JP17") (pin "3") (pinfunction "3_3") (pintype "passive"))
    )
    (net (code "214") (name "unconnected-(JP17-Pad4)") (class "Default")
      (node (ref "JP17") (pin "4") (pinfunction "4_4") (pintype "passive"))
    )
    (net (code "215") (name "unconnected-(JP17-Pad5)") (class "Default")
      (node (ref "JP17") (pin "5") (pinfunction "5_5") (pintype "passive"))
    )
    (net (code "216") (name "unconnected-(JP17-Pad6)") (class "Default")
      (node (ref "JP17") (pin "6") (pinfunction "6_6") (pintype "passive"))
    )
    (net (code "217") (name "unconnected-(JP17-Pad7)") (class "Default")
      (node (ref "JP17") (pin "7") (pinfunction "7_7") (pintype "passive"))
    )
    (net (code "218") (name "unconnected-(JP17-Pad8)") (class "Default")
      (node (ref "JP17") (pin "8") (pinfunction "8_8") (pintype "passive"))
    )
    (net (code "219") (name "unconnected-(JP17-Pad9)") (class "Default")
      (node (ref "JP17") (pin "9") (pinfunction "9_9") (pintype "passive"))
    )
    (net (code "220") (name "unconnected-(JP17-Pad10)") (class "Default")
      (node (ref "JP17") (pin "10") (pinfunction "10_10") (pintype "passive"))
    )
    (net (code "221") (name "unconnected-(JP17-Pad11)") (class "Default")
      (node (ref "JP17") (pin "11") (pinfunction "11_11") (pintype "passive"))
    )
    (net (code "222") (name "unconnected-(JP17-Pad12)") (class "Default")
      (node (ref "JP17") (pin "12") (pinfunction "12_12") (pintype "passive"))
    )
    (net (code "223") (name "unconnected-(JP18-Pad1)") (class "Default")
      (node (ref "JP18") (pin "1") (pinfunction "1_1") (pintype "passive"))
    )
    (net (code "224") (name "unconnected-(JP18-Pad2)") (class "Default")
      (node (ref "JP18") (pin "2") (pinfunction "2_2") (pintype "passive"))
    )
    (net (code "225") (name "unconnected-(JP18-Pad3)") (class "Default")
      (node (ref "JP18") (pin "3") (pinfunction "3_3") (pintype "passive"))
    )
    (net (code "226") (name "unconnected-(JP18-Pad4)") (class "Default")
      (node (ref "JP18") (pin "4") (pinfunction "4_4") (pintype "passive"))
    )
    (net (code "227") (name "unconnected-(JP18-Pad5)") (class "Default")
      (node (ref "JP18") (pin "5") (pinfunction "5_5") (pintype "passive"))
    )
    (net (code "228") (name "unconnected-(JP18-Pad6)") (class "Default")
      (node (ref "JP18") (pin "6") (pinfunction "6_6") (pintype "passive"))
    )
    (net (code "229") (name "unconnected-(JP18-Pad7)") (class "Default")
      (node (ref "JP18") (pin "7") (pinfunction "7_7") (pintype "passive"))
    )
    (net (code "230") (name "unconnected-(JP18-Pad8)") (class "Default")
      (node (ref "JP18") (pin "8") (pinfunction "8_8") (pintype "passive"))
    )
    (net (code "231") (name "unconnected-(JP18-Pad9)") (class "Default")
      (node (ref "JP18") (pin "9") (pinfunction "9_9") (pintype "passive"))
    )
    (net (code "232") (name "unconnected-(JP18-Pad10)") (class "Default")
      (node (ref "JP18") (pin "10") (pinfunction "10_10") (pintype "passive"))
    )
    (net (code "233") (name "unconnected-(JP18-Pad11)") (class "Default")
      (node (ref "JP18") (pin "11") (pinfunction "11_11") (pintype "passive"))
    )
    (net (code "234") (name "unconnected-(JP18-Pad12)") (class "Default")
      (node (ref "JP18") (pin "12") (pinfunction "12_12") (pintype "passive"))
    )
    (net (code "235") (name "unconnected-(JP19-Pad1)") (class "Default")
      (node (ref "JP19") (pin "1") (pinfunction "1_1") (pintype "passive"))
    )
    (net (code "236") (name "unconnected-(JP19-Pad2)") (class "Default")
      (node (ref "JP19") (pin "2") (pinfunction "2_2") (pintype "passive"))
    )
    (net (code "237") (name "unconnected-(JP19-Pad3)") (class "Default")
      (node (ref "JP19") (pin "3") (pinfunction "3_3") (pintype "passive"))
    )
    (net (code "238") (name "unconnected-(JP19-Pad4)") (class "Default")
      (node (ref "JP19") (pin "4") (pinfunction "4_4") (pintype "passive"))
    )
    (net (code "239") (name "unconnected-(JP19-Pad5)") (class "Default")
      (node (ref "JP19") (pin "5") (pinfunction "5_5") (pintype "passive"))
    )
    (net (code "240") (name "unconnected-(JP19-Pad6)") (class "Default")
      (node (ref "JP19") (pin "6") (pinfunction "6_6") (pintype "passive"))
    )
    (net (code "241") (name "unconnected-(JP19-Pad7)") (class "Default")
      (node (ref "JP19") (pin "7") (pinfunction "7_7") (pintype "passive"))
    )
    (net (code "242") (name "unconnected-(JP19-Pad8)") (class "Default")
      (node (ref "JP19") (pin "8") (pinfunction "8_8") (pintype "passive"))
    )
    (net (code "243") (name "unconnected-(JP19-Pad9)") (class "Default")
      (node (ref "JP19") (pin "9") (pinfunction "9_9") (pintype "passive"))
    )
    (net (code "244") (name "unconnected-(JP19-Pad10)") (class "Default")
      (node (ref "JP19") (pin "10") (pinfunction "10_10") (pintype "passive"))
    )
    (net (code "245") (name "unconnected-(JP19-Pad11)") (class "Default")
      (node (ref "JP19") (pin "11") (pinfunction "11_11") (pintype "passive"))
    )
    (net (code "246") (name "unconnected-(JP19-Pad12)") (class "Default")
      (node (ref "JP19") (pin "12") (pinfunction "12_12") (pintype "passive"))
    )
    (net (code "247") (name "unconnected-(JP20-Pad1)") (class "Default")
      (node (ref "JP20") (pin "1") (pinfunction "1_1") (pintype "passive"))
    )
    (net (code "248") (name "unconnected-(JP20-Pad2)") (class "Default")
      (node (ref "JP20") (pin "2") (pinfunction "2_2") (pintype "passive"))
    )
    (net (code "249") (name "unconnected-(JP20-Pad3)") (class "Default")
      (node (ref "JP20") (pin "3") (pinfunction "3_3") (pintype "passive"))
    )
    (net (code "250") (name "unconnected-(JP20-Pad4)") (class "Default")
      (node (ref "JP20") (pin "4") (pinfunction "4_4") (pintype "passive"))
    )
    (net (code "251") (name "unconnected-(JP20-Pad5)") (class "Default")
      (node (ref "JP20") (pin "5") (pinfunction "5_5") (pintype "passive"))
    )
    (net (code "252") (name "unconnected-(JP20-Pad6)") (class "Default")
      (node (ref "JP20") (pin "6") (pinfunction "6_6") (pintype "passive"))
    )
    (net (code "253") (name "unconnected-(JP20-Pad7)") (class "Default")
      (node (ref "JP20") (pin "7") (pinfunction "7_7") (pintype "passive"))
    )
    (net (code "254") (name "unconnected-(JP20-Pad8)") (class "Default")
      (node (ref "JP20") (pin "8") (pinfunction "8_8") (pintype "passive"))
    )
    (net (code "255") (name "unconnected-(JP20-Pad9)") (class "Default")
      (node (ref "JP20") (pin "9") (pinfunction "9_9") (pintype "passive"))
    )
    (net (code "256") (name "unconnected-(JP20-Pad10)") (class "Default")
      (node (ref "JP20") (pin "10") (pinfunction "10_10") (pintype "passive"))
    )
    (net (code "257") (name "unconnected-(JP20-Pad11)") (class "Default")
      (node (ref "JP20") (pin "11") (pinfunction "11_11") (pintype "passive"))
    )
    (net (code "258") (name "unconnected-(JP20-Pad12)") (class "Default")
      (node (ref "JP20") (pin "12") (pinfunction "12_12") (pintype "passive"))
    )
    (net (code "259") (name "unconnected-(JP21-Pad1)") (class "Default")
      (node (ref "JP21") (pin "1") (pinfunction "1_1") (pintype "passive"))
    )
    (net (code "260") (name "unconnected-(JP21-Pad2)") (class "Default")
      (node (ref "JP21") (pin "2") (pinfunction "2_2") (pintype "passive"))
    )
    (net (code "261") (name "unconnected-(JP21-Pad3)") (class "Default")
      (node (ref "JP21") (pin "3") (pinfunction "3_3") (pintype "passive"))
    )
    (net (code "262") (name "unconnected-(JP21-Pad4)") (class "Default")
      (node (ref "JP21") (pin "4") (pinfunction "4_4") (pintype "passive"))
    )
    (net (code "263") (name "unconnected-(JP21-Pad5)") (class "Default")
      (node (ref "JP21") (pin "5") (pinfunction "5_5") (pintype "passive"))
    )
    (net (code "264") (name "unconnected-(JP21-Pad6)") (class "Default")
      (node (ref "JP21") (pin "6") (pinfunction "6_6") (pintype "passive"))
    )
    (net (code "265") (name "unconnected-(JP21-Pad7)") (class "Default")
      (node (ref "JP21") (pin "7") (pinfunction "7_7") (pintype "passive"))
    )
    (net (code "266") (name "unconnected-(JP21-Pad8)") (class "Default")
      (node (ref "JP21") (pin "8") (pinfunction "8_8") (pintype "passive"))
    )
    (net (code "267") (name "unconnected-(JP21-Pad9)") (class "Default")
      (node (ref "JP21") (pin "9") (pinfunction "9_9") (pintype "passive"))
    )
    (net (code "268") (name "unconnected-(JP21-Pad10)") (class "Default")
      (node (ref "JP21") (pin "10") (pinfunction "10_10") (pintype "passive"))
    )
    (net (code "269") (name "unconnected-(JP21-Pad11)") (class "Default")
      (node (ref "JP21") (pin "11") (pinfunction "11_11") (pintype "passive"))
    )
    (net (code "270") (name "unconnected-(JP21-Pad12)") (class "Default")
      (node (ref "JP21") (pin "12") (pinfunction "12_12") (pintype "passive"))
    )
    (net (code "271") (name "unconnected-(JP22-Pad1)") (class "Default")
      (node (ref "JP22") (pin "1") (pinfunction "1_1") (pintype "passive"))
    )
    (net (code "272") (name "unconnected-(JP22-Pad2)") (class "Default")
      (node (ref "JP22") (pin "2") (pinfunction "2_2") (pintype "passive"))
    )
    (net (code "273") (name "unconnected-(JP22-Pad3)") (class "Default")
      (node (ref "JP22") (pin "3") (pinfunction "3_3") (pintype "passive"))
    )
    (net (code "274") (name "unconnected-(JP22-Pad4)") (class "Default")
      (node (ref "JP22") (pin "4") (pinfunction "4_4") (pintype "passive"))
    )
    (net (code "275") (name "unconnected-(JP22-Pad5)") (class "Default")
      (node (ref "JP22") (pin "5") (pinfunction "5_5") (pintype "passive"))
    )
    (net (code "276") (name "unconnected-(JP22-Pad6)") (class "Default")
      (node (ref "JP22") (pin "6") (pinfunction "6_6") (pintype "passive"))
    )
    (net (code "277") (name "unconnected-(JP22-Pad7)") (class "Default")
      (node (ref "JP22") (pin "7") (pinfunction "7_7") (pintype "passive"))
    )
    (net (code "278") (name "unconnected-(JP22-Pad8)") (class "Default")
      (node (ref "JP22") (pin "8") (pinfunction "8_8") (pintype "passive"))
    )
    (net (code "279") (name "unconnected-(JP22-Pad9)") (class "Default")
      (node (ref "JP22") (pin "9") (pinfunction "9_9") (pintype "passive"))
    )
    (net (code "280") (name "unconnected-(JP22-Pad10)") (class "Default")
      (node (ref "JP22") (pin "10") (pinfunction "10_10") (pintype "passive"))
    )
    (net (code "281") (name "unconnected-(JP22-Pad11)") (class "Default")
      (node (ref "JP22") (pin "11") (pinfunction "11_11") (pintype "passive"))
    )
    (net (code "282") (name "unconnected-(JP22-Pad12)") (class "Default")
      (node (ref "JP22") (pin "12") (pinfunction "12_12") (pintype "passive"))
    )
    (net (code "283") (name "unconnected-(JP22-Pad13)") (class "Default")
      (node (ref "JP22") (pin "13") (pinfunction "13_13") (pintype "passive"))
    )
    (net (code "284") (name "unconnected-(JP22-Pad14)") (class "Default")
      (node (ref "JP22") (pin "14") (pinfunction "14_14") (pintype "passive"))
    )
    (net (code "285") (name "unconnected-(JP22-Pad15)") (class "Default")
      (node (ref "JP22") (pin "15") (pinfunction "15_15") (pintype "passive"))
    )
    (net (code "286") (name "unconnected-(JP22-Pad16)") (class "Default")
      (node (ref "JP22") (pin "16") (pinfunction "16_16") (pintype "passive"))
    )
    (net (code "287") (name "unconnected-(JP23-Pad1)") (class "Default")
      (node (ref "JP23") (pin "1") (pinfunction "1_1") (pintype "passive"))
    )
    (net (code "288") (name "unconnected-(JP23-Pad2)") (class "Default")
      (node (ref "JP23") (pin "2") (pinfunction "2_2") (pintype "passive"))
    )
    (net (code "289") (name "unconnected-(JP23-Pad3)") (class "Default")
      (node (ref "JP23") (pin "3") (pinfunction "3_3") (pintype "passive"))
    )
    (net (code "290") (name "unconnected-(JP23-Pad4)") (class "Default")
      (node (ref "JP23") (pin "4") (pinfunction "4_4") (pintype "passive"))
    )
    (net (code "291") (name "unconnected-(JP23-Pad5)") (class "Default")
      (node (ref "JP23") (pin "5") (pinfunction "5_5") (pintype "passive"))
    )
    (net (code "292") (name "unconnected-(JP23-Pad6)") (class "Default")
      (node (ref "JP23") (pin "6") (pinfunction "6_6") (pintype "passive"))
    )
    (net (code "293") (name "unconnected-(JP23-Pad7)") (class "Default")
      (node (ref "JP23") (pin "7") (pinfunction "7_7") (pintype "passive"))
    )
    (net (code "294") (name "unconnected-(JP23-Pad8)") (class "Default")
      (node (ref "JP23") (pin "8") (pinfunction "8_8") (pintype "passive"))
    )
    (net (code "295") (name "unconnected-(JP23-Pad9)") (class "Default")
      (node (ref "JP23") (pin "9") (pinfunction "9_9") (pintype "passive"))
    )
    (net (code "296") (name "unconnected-(JP23-Pad10)") (class "Default")
      (node (ref "JP23") (pin "10") (pinfunction "10_10") (pintype "passive"))
    )
    (net (code "297") (name "unconnected-(JP23-Pad11)") (class "Default")
      (node (ref "JP23") (pin "11") (pinfunction "11_11") (pintype "passive"))
    )
    (net (code "298") (name "unconnected-(JP23-Pad12)") (class "Default")
      (node (ref "JP23") (pin "12") (pinfunction "12_12") (pintype "passive"))
    )
    (net (code "299") (name "unconnected-(JP24-Pad1)") (class "Default")
      (node (ref "JP24") (pin "1") (pinfunction "1_1") (pintype "passive"))
    )
    (net (code "300") (name "unconnected-(JP24-Pad2)") (class "Default")
      (node (ref "JP24") (pin "2") (pinfunction "2_2") (pintype "passive"))
    )
    (net (code "301") (name "unconnected-(JP24-Pad3)") (class "Default")
      (node (ref "JP24") (pin "3") (pinfunction "3_3") (pintype "passive"))
    )
    (net (code "302") (name "unconnected-(JP24-Pad4)") (class "Default")
      (node (ref "JP24") (pin "4") (pinfunction "4_4") (pintype "passive"))
    )
    (net (code "303") (name "unconnected-(JP24-Pad5)") (class "Default")
      (node (ref "JP24") (pin "5") (pinfunction "5_5") (pintype "passive"))
    )
    (net (code "304") (name "unconnected-(JP24-Pad6)") (class "Default")
      (node (ref "JP24") (pin "6") (pinfunction "6_6") (pintype "passive"))
    )
    (net (code "305") (name "unconnected-(JP24-Pad7)") (class "Default")
      (node (ref "JP24") (pin "7") (pinfunction "7_7") (pintype "passive"))
    )
    (net (code "306") (name "unconnected-(JP24-Pad8)") (class "Default")
      (node (ref "JP24") (pin "8") (pinfunction "8_8") (pintype "passive"))
    )
    (net (code "307") (name "unconnected-(JP24-Pad9)") (class "Default")
      (node (ref "JP24") (pin "9") (pinfunction "9_9") (pintype "passive"))
    )
    (net (code "308") (name "unconnected-(JP24-Pad10)") (class "Default")
      (node (ref "JP24") (pin "10") (pinfunction "10_10") (pintype "passive"))
    )
    (net (code "309") (name "unconnected-(JP24-Pad11)") (class "Default")
      (node (ref "JP24") (pin "11") (pinfunction "11_11") (pintype "passive"))
    )
    (net (code "310") (name "unconnected-(JP24-Pad12)") (class "Default")
      (node (ref "JP24") (pin "12") (pinfunction "12_12") (pintype "passive"))
    )
  )
)
